# USBHost.net
KiCad netlist of a schematic drawn in EAGLE
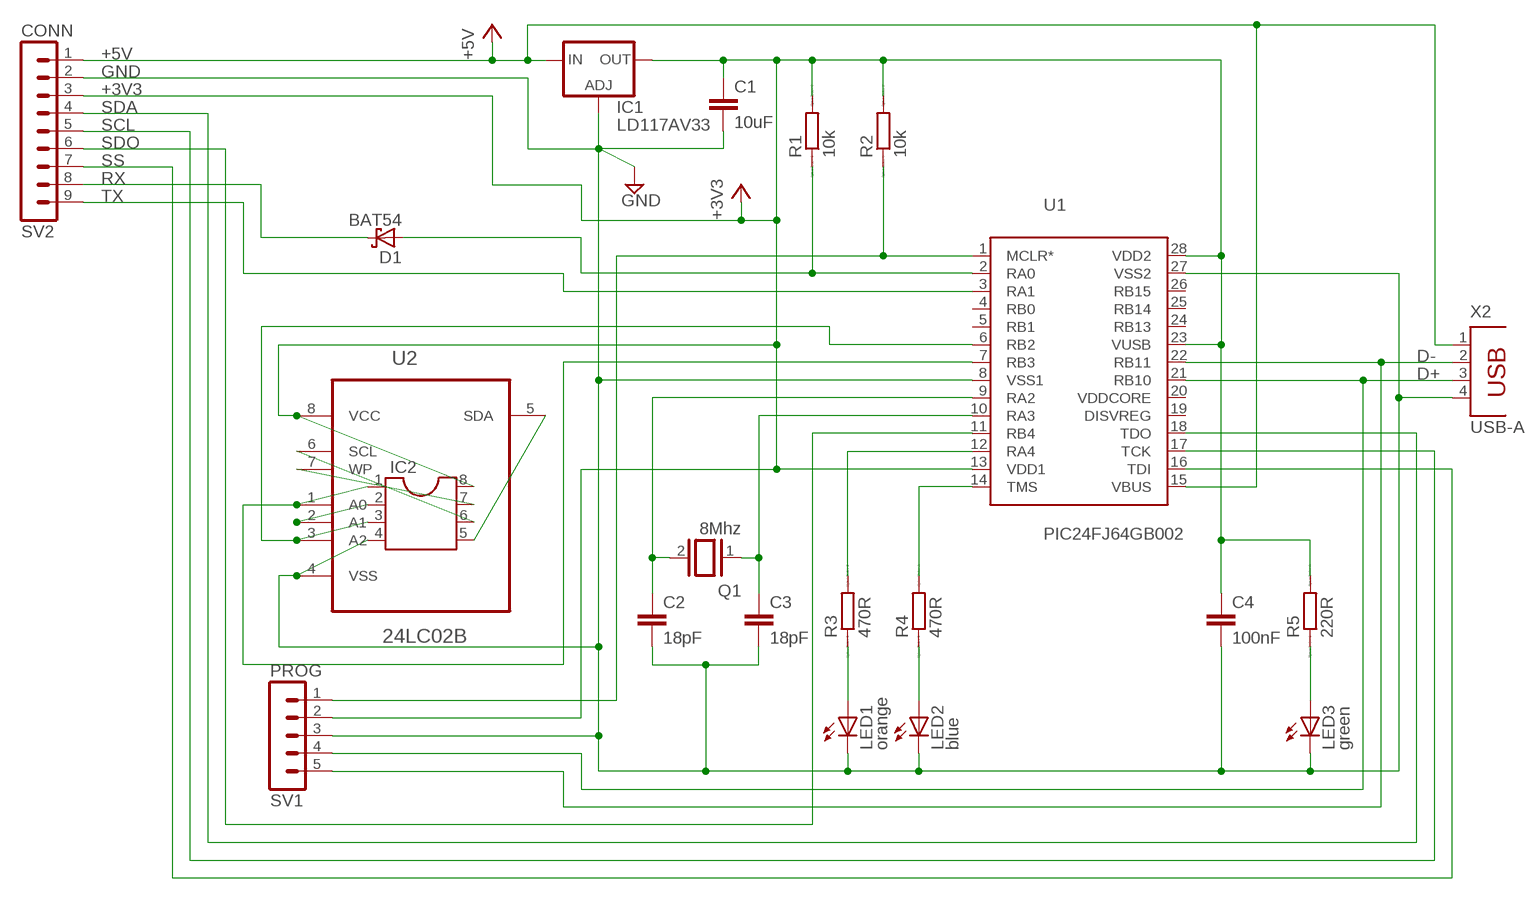
[diagram p0: schematic, sheet 1]

(export (version "E")
  (design (tool "Eeschema 10.0.6"))
  (components
    (comp (ref "C1")
      (value "10uF")
      (footprint "eagle-import:C025-025X050")
      (libsource (lib "eagle-import") (part "C-EU025-025X050"))
    )
    (comp (ref "C2")
      (value "18pF")
      (footprint "eagle-import:C025-025X050")
      (libsource (lib "eagle-import") (part "C-EU025-025X050"))
    )
    (comp (ref "C3")
      (value "18pF")
      (footprint "eagle-import:C025-025X050")
      (libsource (lib "eagle-import") (part "C-EU025-025X050"))
    )
    (comp (ref "C4")
      (value "100nF")
      (footprint "eagle-import:C025-025X050")
      (libsource (lib "eagle-import") (part "C-EU025-025X050"))
    )
    (comp (ref "D1")
      (value "BAT54")
      (footprint "eagle-import:DO35-7")
      (libsource (lib "eagle-import") (part "SCHOTTKY-DIODEDO35-7"))
    )
    (comp (ref "IC1")
      (value "LD117AV33")
      (footprint "eagle-import:TO220L1")
      (libsource (lib "eagle-import") (part "LD117A?V33"))
    )
    (comp (ref "IC2")
      (value "DIL8S")
      (footprint "eagle-import:SOCKET-08")
      (libsource (lib "eagle-import") (part "DIL8S"))
    )
    (comp (ref "LED1")
      (value "orange")
      (footprint "eagle-import:LED5MM")
      (libsource (lib "eagle-import") (part "LED5MM"))
    )
    (comp (ref "LED2")
      (value "blue")
      (footprint "eagle-import:LED5MM")
      (libsource (lib "eagle-import") (part "LED5MM"))
    )
    (comp (ref "LED3")
      (value "green")
      (footprint "eagle-import:LED5MM")
      (libsource (lib "eagle-import") (part "LED5MM"))
    )
    (comp (ref "Q1")
      (value "8Mhz")
      (footprint "eagle-import:QS")
      (libsource (lib "eagle-import") (part "XTAL/S"))
    )
    (comp (ref "R1")
      (value "10k")
      (footprint "eagle-import:0204_7")
      (libsource (lib "eagle-import") (part "R0204/7"))
    )
    (comp (ref "R2")
      (value "10k")
      (footprint "eagle-import:0204_7")
      (libsource (lib "eagle-import") (part "R0204/7"))
    )
    (comp (ref "R3")
      (value "470R")
      (footprint "eagle-import:0204_7")
      (libsource (lib "eagle-import") (part "R0204/7"))
    )
    (comp (ref "R4")
      (value "470R")
      (footprint "eagle-import:0204_7")
      (libsource (lib "eagle-import") (part "R0204/7"))
    )
    (comp (ref "R5")
      (value "220R")
      (footprint "eagle-import:0204_7")
      (libsource (lib "eagle-import") (part "R0204/7"))
    )
    (comp (ref "SV1")
      (value "PROG")
      (footprint "eagle-import:MA05-1")
      (libsource (lib "eagle-import") (part "MA05-1"))
    )
    (comp (ref "SV2")
      (value "CONN")
      (footprint "eagle-import:MA09-1")
      (libsource (lib "eagle-import") (part "MA09-1"))
    )
    (comp (ref "U1")
      (value "PIC24FJ64GB002")
      (footprint "eagle-import:DIP254P762X508-28")
      (fields (field (name "MPN") "PIC24FJ64GB002-I/SP"))
      (libsource (lib "eagle-import") (part "PIC24FJ64GB002-I/SP"))
    )
    (comp (ref "U2")
      (value "24LC02B")
      (footprint "eagle-import:SOIC127P600X175-8N")
      (fields (field (name "MPN") "24LC02B-I/SNG"))
      (libsource (lib "eagle-import") (part "24LC/SN02B-I"))
    )
    (comp (ref "X2")
      (value "USB-A")
      (footprint "eagle-import:PN87520")
      (libsource (lib "eagle-import") (part "PN87520"))
    )
  )
  (nets
    (net (code "1") (name "+3V3") (class "Default")
      (node (ref "C1") (pin "1") (pinfunction "1_1") (pintype "passive"))
      (node (ref "C4") (pin "1") (pinfunction "1_1") (pintype "passive"))
      (node (ref "IC1") (pin "2") (pinfunction "OUT_2") (pintype "passive"))
      (node (ref "IC2") (pin "8") (pinfunction "8_8") (pintype "passive"))
      (node (ref "R1") (pin "2") (pinfunction "2_2") (pintype "passive"))
      (node (ref "R2") (pin "2") (pinfunction "2_2") (pintype "passive"))
      (node (ref "R5") (pin "2") (pinfunction "2_2") (pintype "passive"))
      (node (ref "SV1") (pin "2") (pinfunction "2_2") (pintype "passive"))
      (node (ref "SV2") (pin "3") (pinfunction "3_3") (pintype "passive"))
      (node (ref "U1") (pin "13") (pinfunction "VDD1_13") (pintype "power_in"))
      (node (ref "U1") (pin "23") (pinfunction "VUSB_23") (pintype "passive"))
      (node (ref "U1") (pin "28") (pinfunction "VDD2_28") (pintype "power_in"))
      (node (ref "U2") (pin "8") (pinfunction "VCC_8") (pintype "power_in"))
    )
    (net (code "2") (name "+5V") (class "Default")
      (node (ref "IC1") (pin "3") (pinfunction "IN_3") (pintype "input"))
      (node (ref "SV2") (pin "1") (pinfunction "1_1") (pintype "passive"))
      (node (ref "U1") (pin "15") (pinfunction "VBUS_15") (pintype "passive"))
      (node (ref "X2") (pin "1") (pinfunction "1_1") (pintype "passive"))
    )
    (net (code "3") (name "/D+") (class "Default")
      (node (ref "SV1") (pin "4") (pinfunction "4_4") (pintype "passive"))
      (node (ref "U1") (pin "21") (pinfunction "RB10_21") (pintype "passive"))
      (node (ref "X2") (pin "3") (pinfunction "3_3") (pintype "passive"))
    )
    (net (code "4") (name "/D-") (class "Default")
      (node (ref "SV1") (pin "5") (pinfunction "5_5") (pintype "passive"))
      (node (ref "U1") (pin "22") (pinfunction "RB11_22") (pintype "passive"))
      (node (ref "X2") (pin "2") (pinfunction "2_2") (pintype "passive"))
    )
    (net (code "5") (name "/RX") (class "Default")
      (node (ref "D1") (pin "C") (pinfunction "C_C") (pintype "passive"))
      (node (ref "SV2") (pin "8") (pinfunction "8_8") (pintype "passive"))
    )
    (net (code "6") (name "/SCL") (class "Default")
      (node (ref "SV2") (pin "5") (pinfunction "5_5") (pintype "passive"))
      (node (ref "U1") (pin "17") (pinfunction "TCK_17") (pintype "input"))
    )
    (net (code "7") (name "/SDA") (class "Default")
      (node (ref "SV2") (pin "4") (pinfunction "4_4") (pintype "passive"))
      (node (ref "U1") (pin "18") (pinfunction "TDO_18") (pintype "output"))
    )
    (net (code "8") (name "/SDO") (class "Default")
      (node (ref "SV2") (pin "6") (pinfunction "6_6") (pintype "passive"))
      (node (ref "U1") (pin "11") (pinfunction "RB4_11") (pintype "bidirectional"))
    )
    (net (code "9") (name "/SS") (class "Default")
      (node (ref "SV2") (pin "7") (pinfunction "7_7") (pintype "passive"))
      (node (ref "U1") (pin "16") (pinfunction "TDI_16") (pintype "input"))
    )
    (net (code "10") (name "/TX") (class "Default")
      (node (ref "SV2") (pin "9") (pinfunction "9_9") (pintype "passive"))
      (node (ref "U1") (pin "3") (pinfunction "RA1_3") (pintype "bidirectional"))
    )
    (net (code "11") (name "/VDDCORE") (class "Default")
      (node (ref "U1") (pin "20") (pinfunction "VDDCORE_20") (pintype "power_in"))
    )
    (net (code "12") (name "GND") (class "Default")
      (node (ref "C1") (pin "2") (pinfunction "2_2") (pintype "passive"))
      (node (ref "C2") (pin "2") (pinfunction "2_2") (pintype "passive"))
      (node (ref "C3") (pin "2") (pinfunction "2_2") (pintype "passive"))
      (node (ref "C4") (pin "2") (pinfunction "2_2") (pintype "passive"))
      (node (ref "IC1") (pin "1") (pinfunction "ADJ_1") (pintype "input"))
      (node (ref "IC2") (pin "4") (pinfunction "4_4") (pintype "passive"))
      (node (ref "LED1") (pin "K") (pinfunction "C_K") (pintype "passive"))
      (node (ref "LED2") (pin "K") (pinfunction "C_K") (pintype "passive"))
      (node (ref "LED3") (pin "K") (pinfunction "C_K") (pintype "passive"))
      (node (ref "SV1") (pin "3") (pinfunction "3_3") (pintype "passive"))
      (node (ref "SV2") (pin "2") (pinfunction "2_2") (pintype "passive"))
      (node (ref "U1") (pin "27") (pinfunction "VSS2_27") (pintype "power_in"))
      (node (ref "U1") (pin "8") (pinfunction "VSS1_8") (pintype "power_in"))
      (node (ref "U2") (pin "4") (pinfunction "VSS_4") (pintype "power_in"))
      (node (ref "X2") (pin "4") (pinfunction "4_4") (pintype "passive"))
    )
    (net (code "13") (name "Net-(LED1-PadA)") (class "Default")
      (node (ref "LED1") (pin "A") (pinfunction "A_A") (pintype "passive"))
      (node (ref "R3") (pin "1") (pinfunction "1_1") (pintype "passive"))
    )
    (net (code "14") (name "Net-(LED2-PadA)") (class "Default")
      (node (ref "LED2") (pin "A") (pinfunction "A_A") (pintype "passive"))
      (node (ref "R4") (pin "1") (pinfunction "1_1") (pintype "passive"))
    )
    (net (code "15") (name "Net-(LED3-PadA)") (class "Default")
      (node (ref "LED3") (pin "A") (pinfunction "A_A") (pintype "passive"))
      (node (ref "R5") (pin "1") (pinfunction "1_1") (pintype "passive"))
    )
    (net (code "16") (name "Net-(U1-MCLR*)") (class "Default")
      (node (ref "R2") (pin "1") (pinfunction "1_1") (pintype "passive"))
      (node (ref "SV1") (pin "1") (pinfunction "1_1") (pintype "passive"))
      (node (ref "U1") (pin "1") (pinfunction "MCLR*_1") (pintype "bidirectional"))
    )
    (net (code "17") (name "Net-(U1-RA0)") (class "Default")
      (node (ref "D1") (pin "A") (pinfunction "A_A") (pintype "passive"))
      (node (ref "R1") (pin "1") (pinfunction "1_1") (pintype "passive"))
      (node (ref "U1") (pin "2") (pinfunction "RA0_2") (pintype "bidirectional"))
    )
    (net (code "18") (name "Net-(U1-RA2)") (class "Default")
      (node (ref "C2") (pin "1") (pinfunction "1_1") (pintype "passive"))
      (node (ref "Q1") (pin "2") (pinfunction "2_2") (pintype "passive"))
      (node (ref "U1") (pin "9") (pinfunction "RA2_9") (pintype "bidirectional"))
    )
    (net (code "19") (name "Net-(U1-RA3)") (class "Default")
      (node (ref "C3") (pin "1") (pinfunction "1_1") (pintype "passive"))
      (node (ref "Q1") (pin "1") (pinfunction "1_1") (pintype "passive"))
      (node (ref "U1") (pin "10") (pinfunction "RA3_10") (pintype "bidirectional"))
    )
    (net (code "20") (name "Net-(U1-RA4)") (class "Default")
      (node (ref "R3") (pin "2") (pinfunction "2_2") (pintype "passive"))
      (node (ref "U1") (pin "12") (pinfunction "RA4_12") (pintype "bidirectional"))
    )
    (net (code "21") (name "Net-(U1-RB2)") (class "Default")
      (node (ref "IC2") (pin "3") (pinfunction "3_3") (pintype "passive"))
      (node (ref "U1") (pin "6") (pinfunction "RB2_6") (pintype "bidirectional"))
      (node (ref "U2") (pin "3") (pinfunction "A2_3") (pintype "input"))
    )
    (net (code "22") (name "Net-(U1-RB3)") (class "Default")
      (node (ref "IC2") (pin "1") (pinfunction "1_1") (pintype "passive"))
      (node (ref "U1") (pin "7") (pinfunction "RB3_7") (pintype "bidirectional"))
      (node (ref "U2") (pin "1") (pinfunction "A0_1") (pintype "input"))
    )
    (net (code "23") (name "Net-(U1-TMS)") (class "Default")
      (node (ref "R4") (pin "2") (pinfunction "2_2") (pintype "passive"))
      (node (ref "U1") (pin "14") (pinfunction "TMS_14") (pintype "input"))
    )
    (net (code "24") (name "Net-(U2-A1)") (class "Default")
      (node (ref "IC2") (pin "2") (pinfunction "2_2") (pintype "passive"))
      (node (ref "U2") (pin "2") (pinfunction "A1_2") (pintype "input"))
    )
    (net (code "25") (name "Net-(U2-SCL)") (class "Default")
      (node (ref "IC2") (pin "6") (pinfunction "6_6") (pintype "passive"))
      (node (ref "U2") (pin "6") (pinfunction "SCL_6") (pintype "input"))
    )
    (net (code "26") (name "Net-(U2-SDA)") (class "Default")
      (node (ref "IC2") (pin "5") (pinfunction "5_5") (pintype "passive"))
      (node (ref "U2") (pin "5") (pinfunction "SDA_5") (pintype "bidirectional"))
    )
    (net (code "27") (name "Net-(U2-WP)") (class "Default")
      (node (ref "IC2") (pin "7") (pinfunction "7_7") (pintype "passive"))
      (node (ref "U2") (pin "7") (pinfunction "WP_7") (pintype "input"))
    )
    (net (code "28") (name "unconnected-(U1-DISVREG-Pad19)") (class "Default")
      (node (ref "U1") (pin "19") (pinfunction "DISVREG_19") (pintype "passive"))
    )
    (net (code "29") (name "unconnected-(U1-RB0-Pad4)") (class "Default")
      (node (ref "U1") (pin "4") (pinfunction "RB0_4") (pintype "bidirectional"))
    )
    (net (code "30") (name "unconnected-(U1-RB1-Pad5)") (class "Default")
      (node (ref "U1") (pin "5") (pinfunction "RB1_5") (pintype "bidirectional"))
    )
    (net (code "31") (name "unconnected-(U1-RB13-Pad24)") (class "Default")
      (node (ref "U1") (pin "24") (pinfunction "RB13_24") (pintype "bidirectional"))
    )
    (net (code "32") (name "unconnected-(U1-RB14-Pad25)") (class "Default")
      (node (ref "U1") (pin "25") (pinfunction "RB14_25") (pintype "bidirectional"))
    )
    (net (code "33") (name "unconnected-(U1-RB15-Pad26)") (class "Default")
      (node (ref "U1") (pin "26") (pinfunction "RB15_26") (pintype "bidirectional"))
    )
  )
)
